# Comm_board_2024_L76.net
KiCad netlist of a schematic drawn in EAGLE
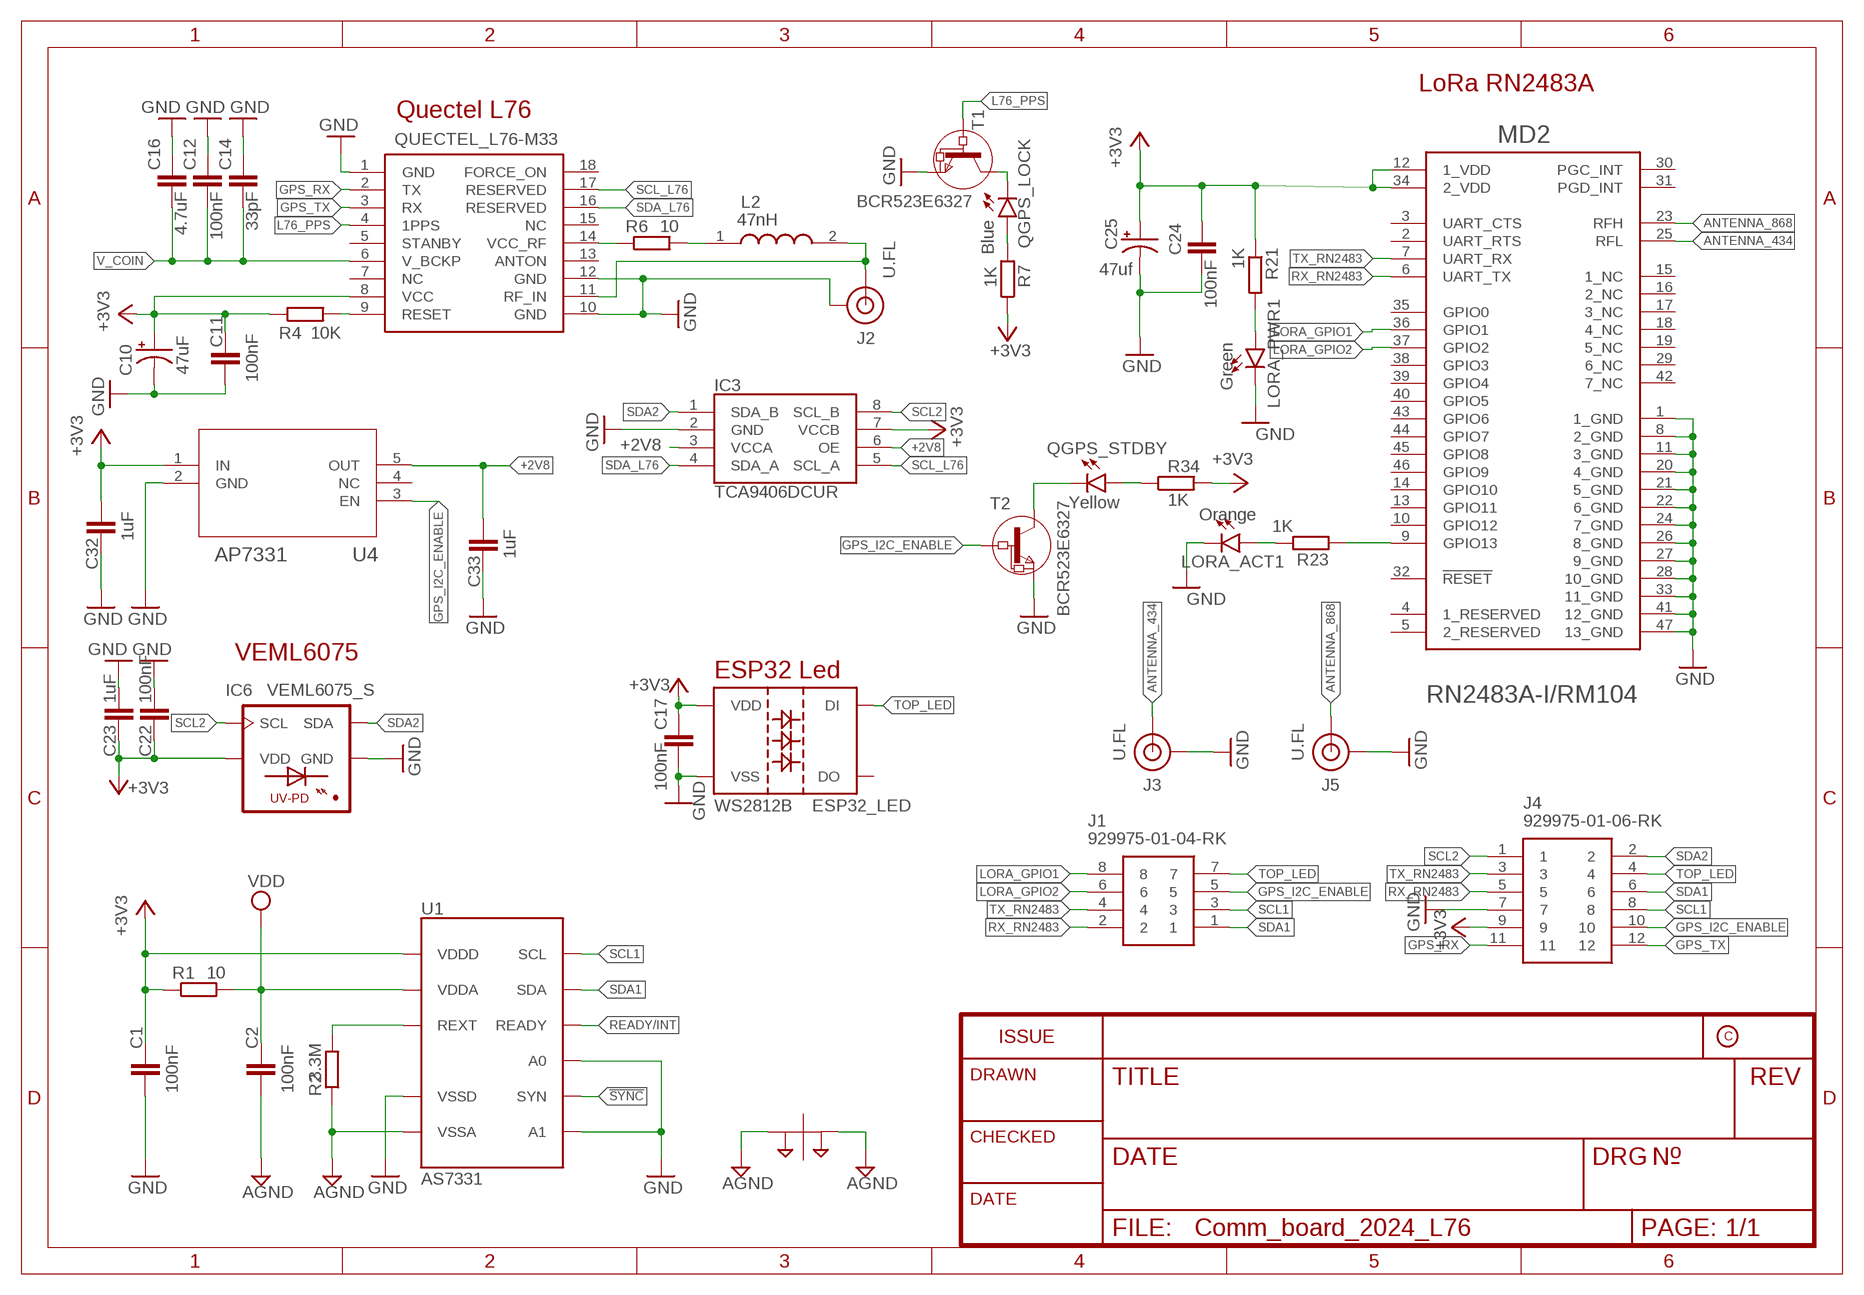
[diagram p0: schematic, sheet 1]

(export (version "E")
  (design (tool "Eeschema 10.0.6"))
  (components
    (comp (ref "C1")
      (value "100nF")
      (footprint "eagle-import:C0603")
      (libsource (lib "eagle-import") (part "C-EUC0603"))
    )
    (comp (ref "C2")
      (value "100nF")
      (footprint "eagle-import:C0603")
      (libsource (lib "eagle-import") (part "C-EUC0603"))
    )
    (comp (ref "C10")
      (value "47uF")
      (footprint "eagle-import:CAPMP6032X250N")
      (fields (field (name "MF") "Vishay") (field (name "MP") "293D226X9025C2TE3"))
      (libsource (lib "eagle-import") (part "293D226X9025C2TE3"))
    )
    (comp (ref "C11")
      (value "100nF")
      (footprint "eagle-import:C0603")
      (libsource (lib "eagle-import") (part "C-EUC0603"))
    )
    (comp (ref "C12")
      (value "100nF")
      (footprint "eagle-import:C0603")
      (libsource (lib "eagle-import") (part "C-EUC0603"))
    )
    (comp (ref "C14")
      (value "33pF")
      (footprint "eagle-import:C0603")
      (libsource (lib "eagle-import") (part "C-EUC0603"))
    )
    (comp (ref "C16")
      (value "4.7uF")
      (footprint "eagle-import:C0603")
      (libsource (lib "eagle-import") (part "C-EUC0603"))
    )
    (comp (ref "C17")
      (value "100nF")
      (footprint "eagle-import:C0603")
      (libsource (lib "eagle-import") (part "C-EUC0603"))
    )
    (comp (ref "C22")
      (value "100nF")
      (footprint "eagle-import:C0603")
      (libsource (lib "eagle-import") (part "C-EUC0603"))
    )
    (comp (ref "C23")
      (value "1uF")
      (footprint "eagle-import:C0603")
      (libsource (lib "eagle-import") (part "C-EUC0603"))
    )
    (comp (ref "C24")
      (value "100nF")
      (footprint "eagle-import:C0603")
      (libsource (lib "eagle-import") (part "C-EUC0603"))
    )
    (comp (ref "C25")
      (value "47uf")
      (footprint "eagle-import:CAPMP6032X250N")
      (fields (field (name "MF") "Vishay") (field (name "MP") "293D226X9025C2TE3"))
      (libsource (lib "eagle-import") (part "293D226X9025C2TE3"))
    )
    (comp (ref "C32")
      (value "1uF")
      (footprint "eagle-import:C0603")
      (libsource (lib "eagle-import") (part "C-EUC0603"))
    )
    (comp (ref "C33")
      (value "1uF")
      (footprint "eagle-import:C0603")
      (libsource (lib "eagle-import") (part "C-EUC0603"))
    )
    (comp (ref "ESP32_LED")
      (value "WS2812B")
      (footprint "eagle-import:WS2812B")
      (libsource (lib "eagle-import") (part "WS2812B"))
    )
    (comp (ref "IC3")
      (value "TCA9406DCUR")
      (footprint "eagle-import:SOP50P310X90-8N")
      (fields (field (name "MOUSER_PART_NUMBER") "595-TCA9406DCUR"))
      (libsource (lib "eagle-import") (part "TCA9406DCUR"))
    )
    (comp (ref "IC6")
      (value "VEML6075_S")
      (footprint "eagle-import:VISHAY_VEML6075_1.25X2X1")
      (fields
        (field (name "DIGI-KEY_PART_NUMBER") "VEML6075CT-ND")
        (field (name "MF") "Vishay Semiconductor")
        (field (name "MP") "VEML6075")
      )
      (libsource (lib "eagle-import") (part "VEML6075_S"))
    )
    (comp (ref "J1")
      (value "929975-01-04-RK")
      (footprint "eagle-import:RHDR8W76P254_2X4_1016X508X839P")
      (fields (field (name "MOUSER_PART_NUMBER") "517-929975-01-04-RK"))
      (libsource (lib "eagle-import") (part "929975-01-04-RK"))
    )
    (comp (ref "J2")
      (value "U.FL")
      (footprint "eagle-import:SPARKFUN-CONNECTORS_SPARKFUN-CONNECTORS_U.FL")
      (libsource (lib "eagle-import") (part "SPARKFUN-CONNECTORS_SPARKFUN-CONNECTORS_U.FL2PIN"))
    )
    (comp (ref "J3")
      (value "U.FL")
      (footprint "eagle-import:SPARKFUN-CONNECTORS_SPARKFUN-CONNECTORS_U.FL")
      (libsource (lib "eagle-import") (part "SPARKFUN-CONNECTORS_SPARKFUN-CONNECTORS_U.FL2PIN"))
    )
    (comp (ref "J4")
      (value "929975-01-06-RK")
      (footprint "eagle-import:RHDR12W76P254_2X6_1524X508X839")
      (fields (field (name "MOUSER_PART_NUMBER") "517-929975-01-06-RK"))
      (libsource (lib "eagle-import") (part "929975-01-06-RK"))
    )
    (comp (ref "J5")
      (value "U.FL")
      (footprint "eagle-import:SPARKFUN-CONNECTORS_SPARKFUN-CONNECTORS_U.FL")
      (libsource (lib "eagle-import") (part "SPARKFUN-CONNECTORS_SPARKFUN-CONNECTORS_U.FL2PIN"))
    )
    (comp (ref "L2")
      (value "47nH")
      (footprint "eagle-import:LQW2UAS12NG00L")
      (fields
        (field (name "MANUFACTURER_PART_NUMBER") "LQW2UAS47NF00L")
        (field (name "MOUSER_PART_NUMBER") "81-LQW2UAS47NF00L")
      )
      (libsource (lib "eagle-import") (part "LQW2UAS47NF00L"))
    )
    (comp (ref "LORA_ACT1")
      (value "Orange")
      (footprint "eagle-import:CHIP-LED0603")
      (libsource (lib "eagle-import") (part "LEDCHIP-LED0603"))
    )
    (comp (ref "LORA_PWR1")
      (value "Green")
      (footprint "eagle-import:CHIP-LED0603")
      (libsource (lib "eagle-import") (part "LEDCHIP-LED0603"))
    )
    (comp (ref "MD2")
      (value "RM104_MICROCHIP_RN2483A-I-RM104MICROCHIP_RN2483A-I-RM104_0_0")
      (footprint "eagle-import:RM104_MICROCHIP_RN2483A-I-RM104_0")
      (fields
        (field (name "DIGIKEY_PART_NUMBER") "RN2483A-I/RM104-ND")
        (field (name "MF") "Microchip")
        (field (name "MOUSER_PART_NUMBER") "579-RN2483A-I/RM104")
      )
      (libsource (lib "eagle-import") (part "RM104_MICROCHIP_RN2483A-I-RM104MICROCHIP_RN2483A-I-RM104_0_0"))
    )
    (comp (ref "QGPS_LOCK")
      (value "Blue")
      (footprint "eagle-import:CHIP-LED0603")
      (libsource (lib "eagle-import") (part "LEDCHIP-LED0603"))
    )
    (comp (ref "QGPS_STDBY")
      (value "Yellow")
      (footprint "eagle-import:CHIP-LED0603")
      (libsource (lib "eagle-import") (part "LEDCHIP-LED0603"))
    )
    (comp (ref "QUECTEL_L76-M33")
      (value "L76 - M33")
      (footprint "eagle-import:L76-M33")
      (libsource (lib "eagle-import") (part "L76-M33"))
    )
    (comp (ref "R1")
      (value "10")
      (footprint "eagle-import:R0603")
      (libsource (lib "eagle-import") (part "R-EU_R0603"))
    )
    (comp (ref "R2")
      (value "3.3M")
      (footprint "eagle-import:R0603")
      (libsource (lib "eagle-import") (part "R-EU_R0603"))
    )
    (comp (ref "R4")
      (value "10K")
      (footprint "eagle-import:R0603")
      (libsource (lib "eagle-import") (part "R-EU_R0603"))
    )
    (comp (ref "R6")
      (value "10")
      (footprint "eagle-import:R0603")
      (libsource (lib "eagle-import") (part "R-EU_R0603"))
    )
    (comp (ref "R7")
      (value "1K")
      (footprint "eagle-import:R0603")
      (libsource (lib "eagle-import") (part "R-EU_R0603"))
    )
    (comp (ref "R21")
      (value "1K")
      (footprint "eagle-import:R0603")
      (libsource (lib "eagle-import") (part "rcl_334_R-EU_R0603"))
    )
    (comp (ref "R23")
      (value "1K")
      (footprint "eagle-import:R0603")
      (libsource (lib "eagle-import") (part "rcl_334_R-EU_R0603"))
    )
    (comp (ref "R34")
      (value "1K")
      (footprint "eagle-import:R0603")
      (libsource (lib "eagle-import") (part "R-EU_R0603"))
    )
    (comp (ref "SUPPLYTIE1")
      (value "SPARKFUN-POWERSYMBOLS_2PT_GND_TIE")
      (footprint "eagle-import:SPARKFUN-POWERSYMBOLS_2PT_GND_TIE")
      (libsource (lib "eagle-import") (part "SPARKFUN-POWERSYMBOLS_2PT_GND_TIE"))
    )
    (comp (ref "T1")
      (value "BCR523E6327")
      (footprint "eagle-import:SOT-23")
      (fields (field (name "MPN") "DSS20201L-7"))
      (libsource (lib "eagle-import") (part "NPNSOT23"))
    )
    (comp (ref "T2")
      (value "BCR523E6327")
      (footprint "eagle-import:SOT-23")
      (fields (field (name "MPN") "DSS20201L-7") (field (name "SPICEPREFIX") "J"))
      (libsource (lib "eagle-import") (part "NPNSOT23"))
    )
    (comp (ref "U1")
      (value "AS7331")
      (footprint "eagle-import:SPARKFUN_QWIIC_UV_SENSOR_AS7331_OLGA16")
      (libsource (lib "eagle-import") (part "SPARKFUN_QWIIC_UV_SENSOR_AS7331_UV_SENSOR_AS7331"))
    )
    (comp (ref "U4")
      (value "AP7331")
      (footprint "eagle-import:SOT25_DIO")
      (fields
        (field (name "MANUFACTURER_PART_NUMBER") "AP7331-28WG-7")
        (field (name "COPYRIGHT") "Copyright (C) 2022 Ultra Librarian. All rights reserved.")
      )
      (libsource (lib "eagle-import") (part "AP7331-28WG-7SOT25_DIO"))
    )
  )
  (nets
    (net (code "1") (name "+2V8") (class "Default")
      (node (ref "C33") (pin "2") (pinfunction "2_2") (pintype "passive"))
      (node (ref "IC3") (pin "3") (pinfunction "VCCA_3") (pintype "bidirectional"))
      (node (ref "IC3") (pin "6") (pinfunction "OE_6") (pintype "bidirectional"))
      (node (ref "U4") (pin "5") (pinfunction "OUT_5") (pintype "output"))
    )
    (net (code "2") (name "+3V3") (class "Default")
      (node (ref "C1") (pin "2") (pinfunction "2_2") (pintype "passive"))
      (node (ref "C10") (pin "1") (pinfunction "+_1") (pintype "passive"))
      (node (ref "C11") (pin "2") (pinfunction "2_2") (pintype "passive"))
      (node (ref "C17") (pin "1") (pinfunction "1_1") (pintype "passive"))
      (node (ref "C22") (pin "2") (pinfunction "2_2") (pintype "passive"))
      (node (ref "C23") (pin "1") (pinfunction "1_1") (pintype "passive"))
      (node (ref "C24") (pin "1") (pinfunction "1_1") (pintype "passive"))
      (node (ref "C25") (pin "1") (pinfunction "+_1") (pintype "passive"))
      (node (ref "C32") (pin "2") (pinfunction "2_2") (pintype "passive"))
      (node (ref "ESP32_LED") (pin "1") (pinfunction "VDD_1") (pintype "bidirectional"))
      (node (ref "IC3") (pin "7") (pinfunction "VCCB_7") (pintype "bidirectional"))
      (node (ref "IC6") (pin "4") (pinfunction "VDD_4") (pintype "power_in"))
      (node (ref "J4") (pin "9") (pinfunction "9_9") (pintype "bidirectional"))
      (node (ref "MD2") (pin "12") (pinfunction "1_VDD_12") (pintype "bidirectional"))
      (node (ref "MD2") (pin "34") (pinfunction "2_VDD_34") (pintype "bidirectional"))
      (node (ref "QUECTEL_L76-M33") (pin "8") (pinfunction "VCC_8") (pintype "bidirectional"))
      (node (ref "R1") (pin "1") (pinfunction "1_1") (pintype "passive"))
      (node (ref "R21") (pin "1") (pinfunction "1_1") (pintype "passive"))
      (node (ref "R34") (pin "2") (pinfunction "2_2") (pintype "passive"))
      (node (ref "R4") (pin "1") (pinfunction "1_1") (pintype "passive"))
      (node (ref "R7") (pin "1") (pinfunction "1_1") (pintype "passive"))
      (node (ref "U1") (pin "10") (pinfunction "VDDD_10") (pintype "power_in"))
      (node (ref "U4") (pin "1") (pinfunction "IN_1") (pintype "input"))
    )
    (net (code "3") (name "/~{SYNC}") (class "Default")
      (node (ref "U1") (pin "8") (pinfunction "SYN_8") (pintype "input"))
    )
    (net (code "4") (name "AGND") (class "Default")
      (node (ref "C2") (pin "1") (pinfunction "1_1") (pintype "passive"))
      (node (ref "R2") (pin "1") (pinfunction "1_1") (pintype "passive"))
      (node (ref "SUPPLYTIE1") (pin "P$1") (pinfunction "P$1_P$1") (pintype "bidirectional"))
      (node (ref "SUPPLYTIE1") (pin "P$2") (pinfunction "P$2_P$2") (pintype "bidirectional"))
      (node (ref "U1") (pin "1") (pinfunction "VSSA_1") (pintype "power_in"))
      (node (ref "U1") (pin "15") (pinfunction "VSSA_15") (pintype "power_in"))
      (node (ref "U1") (pin "16") (pinfunction "VSSA_16") (pintype "power_in"))
      (node (ref "U1") (pin "2") (pinfunction "VSSA_2") (pintype "power_in"))
      (node (ref "U1") (pin "5") (pinfunction "VSSA_5") (pintype "power_in"))
      (node (ref "U1") (pin "6") (pinfunction "VSSA_6") (pintype "power_in"))
    )
    (net (code "5") (name "ANTENNA_434") (class "Default")
      (node (ref "J3") (pin "FEED") (pinfunction "SIGNAL_FEED") (pintype "bidirectional"))
      (node (ref "MD2") (pin "25") (pinfunction "RFL_25") (pintype "bidirectional"))
    )
    (net (code "6") (name "ANTENNA_868") (class "Default")
      (node (ref "J5") (pin "FEED") (pinfunction "SIGNAL_FEED") (pintype "bidirectional"))
      (node (ref "MD2") (pin "23") (pinfunction "RFH_23") (pintype "bidirectional"))
    )
    (net (code "7") (name "GND") (class "Default")
      (node (ref "C1") (pin "1") (pinfunction "1_1") (pintype "passive"))
      (node (ref "C10") (pin "2") (pinfunction "-_2") (pintype "passive"))
      (node (ref "C11") (pin "1") (pinfunction "1_1") (pintype "passive"))
      (node (ref "C12") (pin "2") (pinfunction "2_2") (pintype "passive"))
      (node (ref "C14") (pin "2") (pinfunction "2_2") (pintype "passive"))
      (node (ref "C16") (pin "2") (pinfunction "2_2") (pintype "passive"))
      (node (ref "C17") (pin "2") (pinfunction "2_2") (pintype "passive"))
      (node (ref "C22") (pin "1") (pinfunction "1_1") (pintype "passive"))
      (node (ref "C23") (pin "2") (pinfunction "2_2") (pintype "passive"))
      (node (ref "C24") (pin "2") (pinfunction "2_2") (pintype "passive"))
      (node (ref "C25") (pin "2") (pinfunction "-_2") (pintype "passive"))
      (node (ref "C32") (pin "1") (pinfunction "1_1") (pintype "passive"))
      (node (ref "C33") (pin "1") (pinfunction "1_1") (pintype "passive"))
      (node (ref "ESP32_LED") (pin "3") (pinfunction "VSS_3") (pintype "bidirectional"))
      (node (ref "IC3") (pin "2") (pinfunction "GND_2") (pintype "bidirectional"))
      (node (ref "IC6") (pin "1") (pinfunction "GND_1") (pintype "power_in"))
      (node (ref "J2") (pin "1") (pinfunction "GND_1") (pintype "bidirectional"))
      (node (ref "J2") (pin "2") (pinfunction "GND_2") (pintype "bidirectional"))
      (node (ref "J2") (pin "3") (pinfunction "GND_3") (pintype "bidirectional"))
      (node (ref "J3") (pin "1") (pinfunction "GND_1") (pintype "bidirectional"))
      (node (ref "J3") (pin "2") (pinfunction "GND_2") (pintype "bidirectional"))
      (node (ref "J3") (pin "3") (pinfunction "GND_3") (pintype "bidirectional"))
      (node (ref "J4") (pin "7") (pinfunction "7_7") (pintype "bidirectional"))
      (node (ref "J5") (pin "1") (pinfunction "GND_1") (pintype "bidirectional"))
      (node (ref "J5") (pin "2") (pinfunction "GND_2") (pintype "bidirectional"))
      (node (ref "J5") (pin "3") (pinfunction "GND_3") (pintype "bidirectional"))
      (node (ref "LORA_ACT1") (pin "C") (pinfunction "C_C") (pintype "passive"))
      (node (ref "LORA_PWR1") (pin "C") (pinfunction "C_C") (pintype "passive"))
      (node (ref "MD2") (pin "1") (pinfunction "1_GND_1") (pintype "bidirectional"))
      (node (ref "MD2") (pin "11") (pinfunction "3_GND_11") (pintype "bidirectional"))
      (node (ref "MD2") (pin "20") (pinfunction "4_GND_20") (pintype "bidirectional"))
      (node (ref "MD2") (pin "21") (pinfunction "5_GND_21") (pintype "bidirectional"))
      (node (ref "MD2") (pin "22") (pinfunction "6_GND_22") (pintype "bidirectional"))
      (node (ref "MD2") (pin "24") (pinfunction "7_GND_24") (pintype "bidirectional"))
      (node (ref "MD2") (pin "26") (pinfunction "8_GND_26") (pintype "bidirectional"))
      (node (ref "MD2") (pin "27") (pinfunction "9_GND_27") (pintype "bidirectional"))
      (node (ref "MD2") (pin "28") (pinfunction "10_GND_28") (pintype "bidirectional"))
      (node (ref "MD2") (pin "33") (pinfunction "11_GND_33") (pintype "bidirectional"))
      (node (ref "MD2") (pin "41") (pinfunction "12_GND_41") (pintype "bidirectional"))
      (node (ref "MD2") (pin "47") (pinfunction "13_GND_47") (pintype "bidirectional"))
      (node (ref "MD2") (pin "8") (pinfunction "2_GND_8") (pintype "bidirectional"))
      (node (ref "QUECTEL_L76-M33") (pin "1") (pinfunction "GND_1") (pintype "bidirectional"))
      (node (ref "QUECTEL_L76-M33") (pin "10") (pinfunction "GND_10") (pintype "bidirectional"))
      (node (ref "QUECTEL_L76-M33") (pin "12") (pinfunction "GND_12") (pintype "bidirectional"))
      (node (ref "T1") (pin "2") (pinfunction "E_2") (pintype "passive"))
      (node (ref "T2") (pin "2") (pinfunction "E_2") (pintype "passive"))
      (node (ref "U1") (pin "11") (pinfunction "VSSD_11") (pintype "power_in"))
      (node (ref "U1") (pin "14") (pinfunction "A0_14") (pintype "input"))
      (node (ref "U1") (pin "7") (pinfunction "A1_7") (pintype "input"))
      (node (ref "U4") (pin "2") (pinfunction "GND_2") (pintype "power_in"))
    )
    (net (code "8") (name "GPS_I2C_ENABLE") (class "Default")
      (node (ref "J1") (pin "5") (pinfunction "5_5") (pintype "bidirectional"))
      (node (ref "J4") (pin "10") (pinfunction "10_10") (pintype "bidirectional"))
      (node (ref "T2") (pin "3") (pinfunction "B_3") (pintype "passive"))
      (node (ref "U4") (pin "3") (pinfunction "EN_3") (pintype "input"))
    )
    (net (code "9") (name "GPS_RX") (class "Default")
      (node (ref "J4") (pin "11") (pinfunction "11_11") (pintype "bidirectional"))
      (node (ref "QUECTEL_L76-M33") (pin "2") (pinfunction "TX_2") (pintype "bidirectional"))
    )
    (net (code "10") (name "GPS_TX") (class "Default")
      (node (ref "J4") (pin "12") (pinfunction "12_12") (pintype "bidirectional"))
      (node (ref "QUECTEL_L76-M33") (pin "3") (pinfunction "RX_3") (pintype "bidirectional"))
    )
    (net (code "11") (name "L76_PPS") (class "Default")
      (node (ref "QUECTEL_L76-M33") (pin "4") (pinfunction "1PPS_4") (pintype "bidirectional"))
      (node (ref "T1") (pin "3") (pinfunction "B_3") (pintype "passive"))
    )
    (net (code "12") (name "LORA_GPIO1") (class "Default")
      (node (ref "J1") (pin "8") (pinfunction "8_8") (pintype "bidirectional"))
      (node (ref "MD2") (pin "36") (pinfunction "GPIO1_36") (pintype "bidirectional"))
    )
    (net (code "13") (name "LORA_GPIO2") (class "Default")
      (node (ref "J1") (pin "6") (pinfunction "6_6") (pintype "bidirectional"))
      (node (ref "MD2") (pin "37") (pinfunction "GPIO2_37") (pintype "bidirectional"))
    )
    (net (code "14") (name "Net-(J2-SIGNAL)") (class "Default")
      (node (ref "J2") (pin "FEED") (pinfunction "SIGNAL_FEED") (pintype "bidirectional"))
      (node (ref "L2") (pin "2") (pinfunction "2_2") (pintype "bidirectional"))
      (node (ref "QUECTEL_L76-M33") (pin "11") (pinfunction "RF_IN_11") (pintype "bidirectional"))
    )
    (net (code "15") (name "Net-(L2-Pad1)") (class "Default")
      (node (ref "L2") (pin "1") (pinfunction "1_1") (pintype "bidirectional"))
      (node (ref "R6") (pin "2") (pinfunction "2_2") (pintype "passive"))
    )
    (net (code "16") (name "Net-(LORA_ACT1-PadA)") (class "Default")
      (node (ref "LORA_ACT1") (pin "A") (pinfunction "A_A") (pintype "passive"))
      (node (ref "R23") (pin "2") (pinfunction "2_2") (pintype "passive"))
    )
    (net (code "17") (name "Net-(LORA_PWR1-PadA)") (class "Default")
      (node (ref "LORA_PWR1") (pin "A") (pinfunction "A_A") (pintype "passive"))
      (node (ref "R21") (pin "2") (pinfunction "2_2") (pintype "passive"))
    )
    (net (code "18") (name "Net-(MD2-GPIO13)") (class "Default")
      (node (ref "MD2") (pin "9") (pinfunction "GPIO13_9") (pintype "bidirectional"))
      (node (ref "R23") (pin "1") (pinfunction "1_1") (pintype "passive"))
    )
    (net (code "19") (name "Net-(QGPS_LOCK-PadA)") (class "Default")
      (node (ref "QGPS_LOCK") (pin "A") (pinfunction "A_A") (pintype "passive"))
      (node (ref "R7") (pin "2") (pinfunction "2_2") (pintype "passive"))
    )
    (net (code "20") (name "Net-(QGPS_STDBY-PadA)") (class "Default")
      (node (ref "QGPS_STDBY") (pin "A") (pinfunction "A_A") (pintype "passive"))
      (node (ref "R34") (pin "1") (pinfunction "1_1") (pintype "passive"))
    )
    (net (code "21") (name "Net-(QUECTEL_L76-M33-RESET)") (class "Default")
      (node (ref "QUECTEL_L76-M33") (pin "9") (pinfunction "RESET_9") (pintype "bidirectional"))
      (node (ref "R4") (pin "2") (pinfunction "2_2") (pintype "passive"))
    )
    (net (code "22") (name "Net-(QUECTEL_L76-M33-VCC_RF)") (class "Default")
      (node (ref "QUECTEL_L76-M33") (pin "14") (pinfunction "VCC_RF_14") (pintype "bidirectional"))
      (node (ref "R6") (pin "1") (pinfunction "1_1") (pintype "passive"))
    )
    (net (code "23") (name "Net-(T1-C)") (class "Default")
      (node (ref "QGPS_LOCK") (pin "C") (pinfunction "C_C") (pintype "passive"))
      (node (ref "T1") (pin "1") (pinfunction "C_1") (pintype "passive"))
    )
    (net (code "24") (name "Net-(T2-C)") (class "Default")
      (node (ref "QGPS_STDBY") (pin "C") (pinfunction "C_C") (pintype "passive"))
      (node (ref "T2") (pin "1") (pinfunction "C_1") (pintype "passive"))
    )
    (net (code "25") (name "Net-(U1-REXT)") (class "Default")
      (node (ref "R2") (pin "2") (pinfunction "2_2") (pintype "passive"))
      (node (ref "U1") (pin "4") (pinfunction "REXT_4") (pintype "bidirectional"))
    )
    (net (code "26") (name "READY{slash}INT") (class "Default")
      (node (ref "U1") (pin "9") (pinfunction "READY_9") (pintype "output"))
    )
    (net (code "27") (name "RX_RN2483") (class "Default")
      (node (ref "J1") (pin "2") (pinfunction "2_2") (pintype "bidirectional"))
      (node (ref "J4") (pin "5") (pinfunction "5_5") (pintype "bidirectional"))
      (node (ref "MD2") (pin "6") (pinfunction "UART_TX_6") (pintype "bidirectional"))
    )
    (net (code "28") (name "SCL1") (class "Default")
      (node (ref "J1") (pin "3") (pinfunction "3_3") (pintype "bidirectional"))
      (node (ref "J4") (pin "8") (pinfunction "8_8") (pintype "bidirectional"))
      (node (ref "U1") (pin "13") (pinfunction "SCL_13") (pintype "input"))
    )
    (net (code "29") (name "SCL2") (class "Default")
      (node (ref "IC3") (pin "8") (pinfunction "SCL_B_8") (pintype "bidirectional"))
      (node (ref "IC6") (pin "3") (pinfunction "SCL_3") (pintype "input"))
      (node (ref "J4") (pin "1") (pinfunction "1_1") (pintype "bidirectional"))
    )
    (net (code "30") (name "SCL_L76") (class "Default")
      (node (ref "IC3") (pin "5") (pinfunction "SCL_A_5") (pintype "bidirectional"))
      (node (ref "QUECTEL_L76-M33") (pin "17") (pinfunction "RESERVED_17") (pintype "bidirectional"))
    )
    (net (code "31") (name "SDA1") (class "Default")
      (node (ref "J1") (pin "1") (pinfunction "1_1") (pintype "bidirectional"))
      (node (ref "J4") (pin "6") (pinfunction "6_6") (pintype "bidirectional"))
      (node (ref "U1") (pin "12") (pinfunction "SDA_12") (pintype "bidirectional"))
    )
    (net (code "32") (name "SDA2") (class "Default")
      (node (ref "IC3") (pin "1") (pinfunction "SDA_B_1") (pintype "bidirectional"))
      (node (ref "IC6") (pin "2") (pinfunction "SDA_2") (pintype "bidirectional"))
      (node (ref "J4") (pin "2") (pinfunction "2_2") (pintype "bidirectional"))
    )
    (net (code "33") (name "SDA_L76") (class "Default")
      (node (ref "IC3") (pin "4") (pinfunction "SDA_A_4") (pintype "bidirectional"))
      (node (ref "QUECTEL_L76-M33") (pin "16") (pinfunction "RESERVED_16") (pintype "bidirectional"))
    )
    (net (code "34") (name "TOP_LED") (class "Default")
      (node (ref "ESP32_LED") (pin "4") (pinfunction "DI_4") (pintype "bidirectional"))
      (node (ref "J1") (pin "7") (pinfunction "7_7") (pintype "bidirectional"))
      (node (ref "J4") (pin "4") (pinfunction "4_4") (pintype "bidirectional"))
    )
    (net (code "35") (name "TX_RN2483") (class "Default")
      (node (ref "J1") (pin "4") (pinfunction "4_4") (pintype "bidirectional"))
      (node (ref "J4") (pin "3") (pinfunction "3_3") (pintype "bidirectional"))
      (node (ref "MD2") (pin "7") (pinfunction "UART_RX_7") (pintype "bidirectional"))
    )
    (net (code "36") (name "VDD") (class "Default")
      (node (ref "C2") (pin "2") (pinfunction "2_2") (pintype "passive"))
      (node (ref "R1") (pin "2") (pinfunction "2_2") (pintype "passive"))
      (node (ref "U1") (pin "3") (pinfunction "VDDA_3") (pintype "power_in"))
    )
    (net (code "37") (name "V_COIN") (class "Default")
      (node (ref "C12") (pin "1") (pinfunction "1_1") (pintype "passive"))
      (node (ref "C14") (pin "1") (pinfunction "1_1") (pintype "passive"))
      (node (ref "C16") (pin "1") (pinfunction "1_1") (pintype "passive"))
      (node (ref "QUECTEL_L76-M33") (pin "6") (pinfunction "V_BCKP_6") (pintype "bidirectional"))
    )
    (net (code "38") (name "unconnected-(ESP32_LED-DO-Pad2)") (class "Default")
      (node (ref "ESP32_LED") (pin "2") (pinfunction "DO_2") (pintype "bidirectional"))
    )
    (net (code "39") (name "unconnected-(MD2-1_NC-Pad15)") (class "Default")
      (node (ref "MD2") (pin "15") (pinfunction "1_NC_15") (pintype "passive"))
    )
    (net (code "40") (name "unconnected-(MD2-1_RESERVED-Pad4)") (class "Default")
      (node (ref "MD2") (pin "4") (pinfunction "1_RESERVED_4") (pintype "passive"))
    )
    (net (code "41") (name "unconnected-(MD2-2_NC-Pad16)") (class "Default")
      (node (ref "MD2") (pin "16") (pinfunction "2_NC_16") (pintype "passive"))
    )
    (net (code "42") (name "unconnected-(MD2-2_RESERVED-Pad5)") (class "Default")
      (node (ref "MD2") (pin "5") (pinfunction "2_RESERVED_5") (pintype "passive"))
    )
    (net (code "43") (name "unconnected-(MD2-3_NC-Pad17)") (class "Default")
      (node (ref "MD2") (pin "17") (pinfunction "3_NC_17") (pintype "passive"))
    )
    (net (code "44") (name "unconnected-(MD2-4_NC-Pad18)") (class "Default")
      (node (ref "MD2") (pin "18") (pinfunction "4_NC_18") (pintype "passive"))
    )
    (net (code "45") (name "unconnected-(MD2-5_NC-Pad19)") (class "Default")
      (node (ref "MD2") (pin "19") (pinfunction "5_NC_19") (pintype "passive"))
    )
    (net (code "46") (name "unconnected-(MD2-6_NC-Pad29)") (class "Default")
      (node (ref "MD2") (pin "29") (pinfunction "6_NC_29") (pintype "passive"))
    )
    (net (code "47") (name "unconnected-(MD2-7_NC-Pad42)") (class "Default")
      (node (ref "MD2") (pin "42") (pinfunction "7_NC_42") (pintype "passive"))
    )
    (net (code "48") (name "unconnected-(MD2-GPIO0-Pad35)") (class "Default")
      (node (ref "MD2") (pin "35") (pinfunction "GPIO0_35") (pintype "bidirectional"))
    )
    (net (code "49") (name "unconnected-(MD2-GPIO3-Pad38)") (class "Default")
      (node (ref "MD2") (pin "38") (pinfunction "GPIO3_38") (pintype "bidirectional"))
    )
    (net (code "50") (name "unconnected-(MD2-GPIO4-Pad39)") (class "Default")
      (node (ref "MD2") (pin "39") (pinfunction "GPIO4_39") (pintype "bidirectional"))
    )
    (net (code "51") (name "unconnected-(MD2-GPIO5-Pad40)") (class "Default")
      (node (ref "MD2") (pin "40") (pinfunction "GPIO5_40") (pintype "bidirectional"))
    )
    (net (code "52") (name "unconnected-(MD2-GPIO6-Pad43)") (class "Default")
      (node (ref "MD2") (pin "43") (pinfunction "GPIO6_43") (pintype "bidirectional"))
    )
    (net (code "53") (name "unconnected-(MD2-GPIO7-Pad44)") (class "Default")
      (node (ref "MD2") (pin "44") (pinfunction "GPIO7_44") (pintype "bidirectional"))
    )
    (net (code "54") (name "unconnected-(MD2-GPIO8-Pad45)") (class "Default")
      (node (ref "MD2") (pin "45") (pinfunction "GPIO8_45") (pintype "bidirectional"))
    )
    (net (code "55") (name "unconnected-(MD2-GPIO9-Pad46)") (class "Default")
      (node (ref "MD2") (pin "46") (pinfunction "GPIO9_46") (pintype "bidirectional"))
    )
    (net (code "56") (name "unconnected-(MD2-GPIO10-Pad14)") (class "Default")
      (node (ref "MD2") (pin "14") (pinfunction "GPIO10_14") (pintype "bidirectional"))
    )
    (net (code "57") (name "unconnected-(MD2-GPIO11-Pad13)") (class "Default")
      (node (ref "MD2") (pin "13") (pinfunction "GPIO11_13") (pintype "bidirectional"))
    )
    (net (code "58") (name "unconnected-(MD2-GPIO12-Pad10)") (class "Default")
      (node (ref "MD2") (pin "10") (pinfunction "GPIO12_10") (pintype "bidirectional"))
    )
    (net (code "59") (name "unconnected-(MD2-PGC_INT-Pad30)") (class "Default")
      (node (ref "MD2") (pin "30") (pinfunction "PGC_INT_30") (pintype "bidirectional"))
    )
    (net (code "60") (name "unconnected-(MD2-PGD_INT-Pad31)") (class "Default")
      (node (ref "MD2") (pin "31") (pinfunction "PGD_INT_31") (pintype "bidirectional"))
    )
    (net (code "61") (name "unconnected-(MD2-UART_CTS-Pad3)") (class "Default")
      (node (ref "MD2") (pin "3") (pinfunction "UART_CTS_3") (pintype "bidirectional"))
    )
    (net (code "62") (name "unconnected-(MD2-UART_RTS-Pad2)") (class "Default")
      (node (ref "MD2") (pin "2") (pinfunction "UART_RTS_2") (pintype "bidirectional"))
    )
    (net (code "63") (name "unconnected-(MD2-~{RESET}-Pad32)") (class "Default")
      (node (ref "MD2") (pin "32") (pinfunction "~{RESET}_32") (pintype "bidirectional"))
    )
    (net (code "64") (name "unconnected-(QUECTEL_L76-M33-ANTON-Pad13)") (class "Default")
      (node (ref "QUECTEL_L76-M33") (pin "13") (pinfunction "ANTON_13") (pintype "bidirectional"))
    )
    (net (code "65") (name "unconnected-(QUECTEL_L76-M33-FORCE_ON-Pad18)") (class "Default")
      (node (ref "QUECTEL_L76-M33") (pin "18") (pinfunction "FORCE_ON_18") (pintype "bidirectional"))
    )
    (net (code "66") (name "unconnected-(QUECTEL_L76-M33-NC-Pad7)") (class "Default")
      (node (ref "QUECTEL_L76-M33") (pin "7") (pinfunction "NC_7") (pintype "bidirectional"))
    )
    (net (code "67") (name "unconnected-(QUECTEL_L76-M33-NC-Pad15)") (class "Default")
      (node (ref "QUECTEL_L76-M33") (pin "15") (pinfunction "NC_15") (pintype "bidirectional"))
    )
    (net (code "68") (name "unconnected-(QUECTEL_L76-M33-STANBY-Pad5)") (class "Default")
      (node (ref "QUECTEL_L76-M33") (pin "5") (pinfunction "STANBY_5") (pintype "bidirectional"))
    )
    (net (code "69") (name "unconnected-(U4-NC-Pad4)") (class "Default")
      (node (ref "U4") (pin "4") (pinfunction "NC_4") (pintype "no_connect"))
    )
  )
)
